# W512A.net
KiCad netlist of a schematic drawn in EAGLE
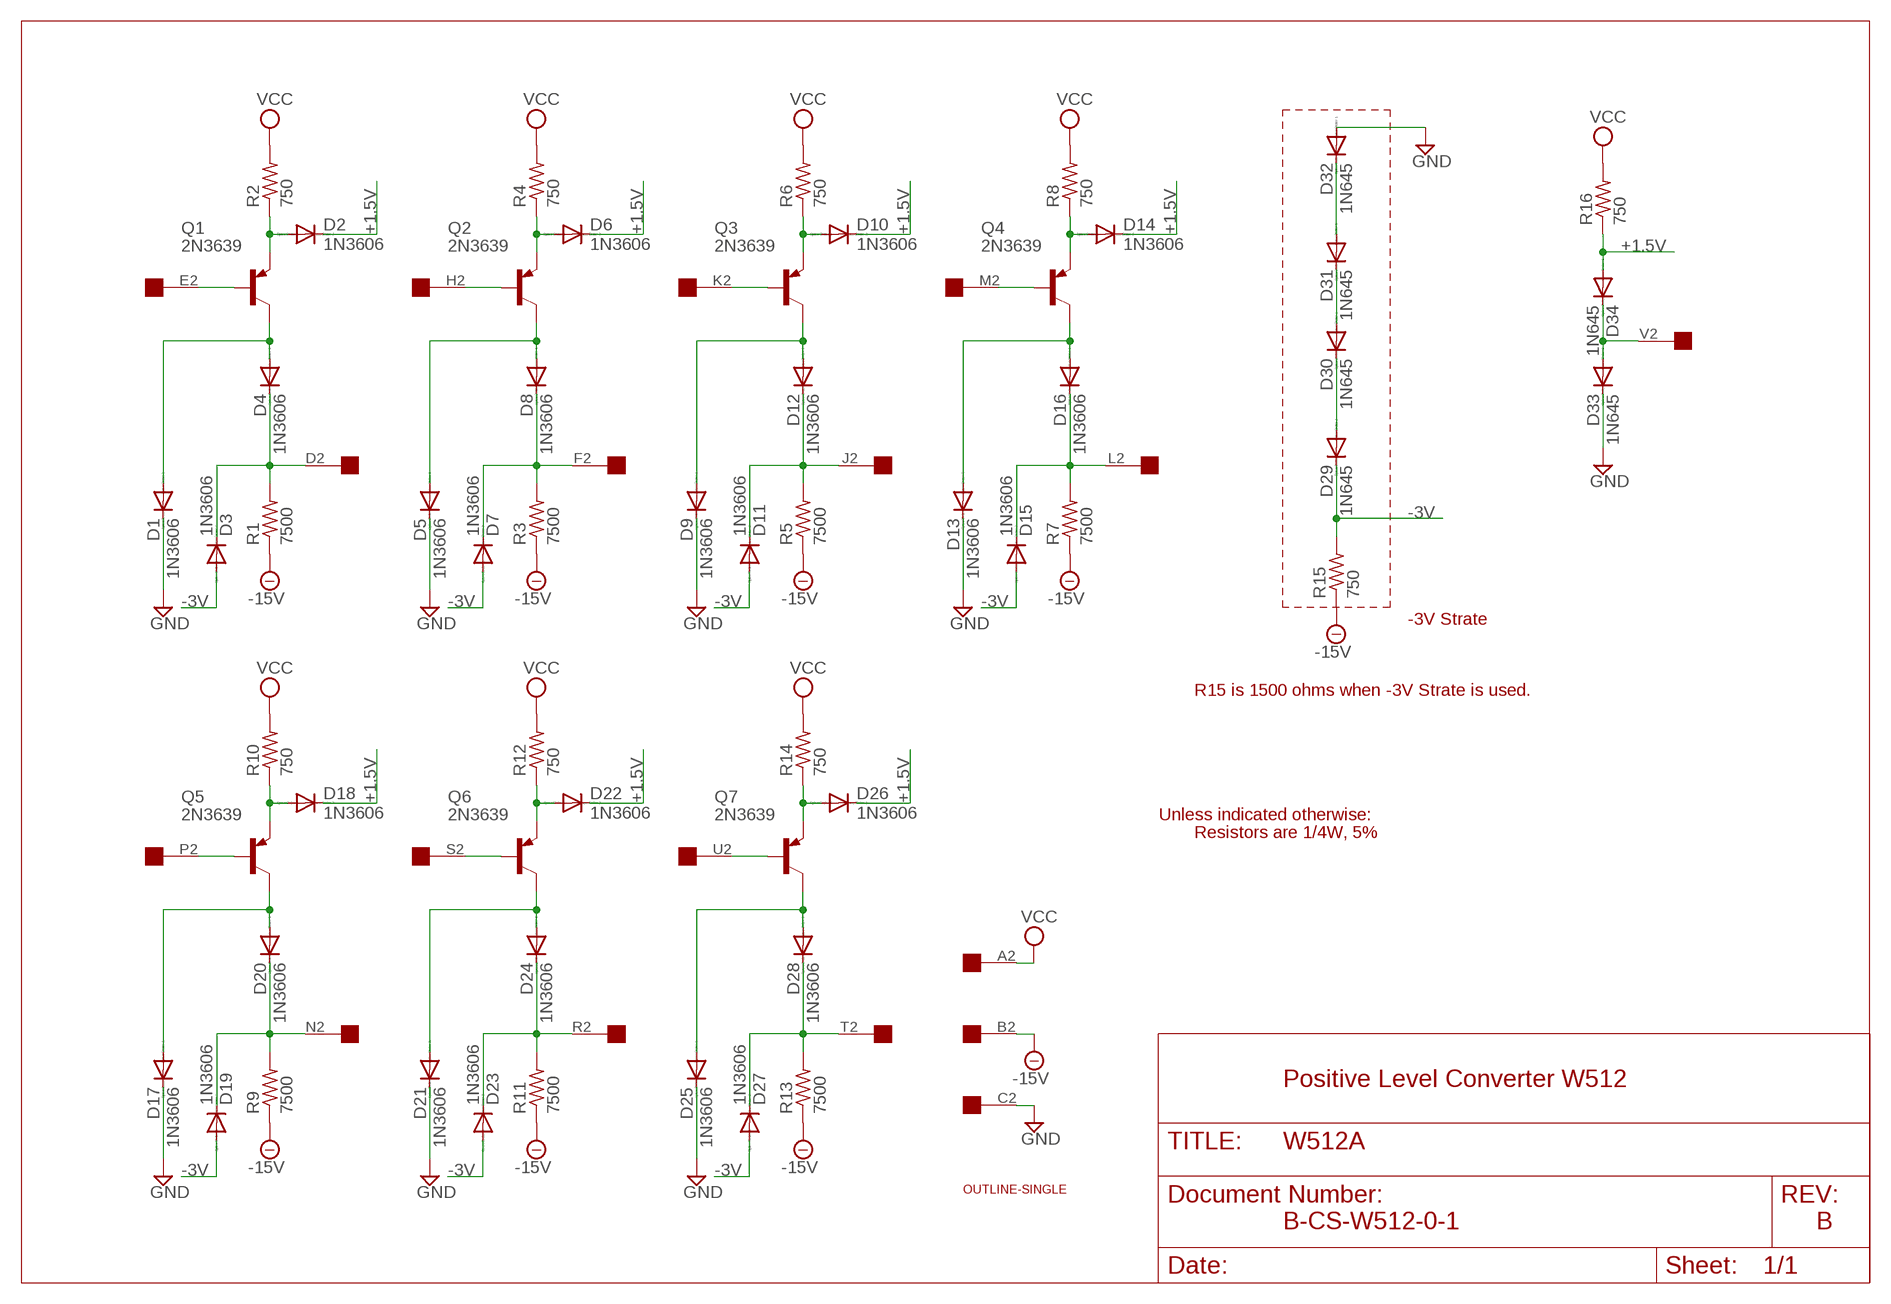
[diagram p0: schematic, sheet 1]

(export (version "E")
  (design (tool "Eeschema 10.0.6"))
  (components
    (comp (ref "D1")
      (value "1N3606")
      (footprint "eagle-import:DO35-10")
      (libsource (lib "eagle-import") (part "1N4148DO35-10"))
    )
    (comp (ref "D2")
      (value "1N3606")
      (footprint "eagle-import:DO35-10")
      (libsource (lib "eagle-import") (part "1N4148DO35-10"))
    )
    (comp (ref "D3")
      (value "1N3606")
      (footprint "eagle-import:DO35-10")
      (libsource (lib "eagle-import") (part "1N4148DO35-10"))
    )
    (comp (ref "D4")
      (value "1N3606")
      (footprint "eagle-import:DO35-10")
      (libsource (lib "eagle-import") (part "1N4148DO35-10"))
    )
    (comp (ref "D5")
      (value "1N3606")
      (footprint "eagle-import:DO35-10")
      (libsource (lib "eagle-import") (part "1N4148DO35-10"))
    )
    (comp (ref "D6")
      (value "1N3606")
      (footprint "eagle-import:DO35-10")
      (libsource (lib "eagle-import") (part "1N4148DO35-10"))
    )
    (comp (ref "D7")
      (value "1N3606")
      (footprint "eagle-import:DO35-10")
      (libsource (lib "eagle-import") (part "1N4148DO35-10"))
    )
    (comp (ref "D8")
      (value "1N3606")
      (footprint "eagle-import:DO35-10")
      (libsource (lib "eagle-import") (part "1N4148DO35-10"))
    )
    (comp (ref "D9")
      (value "1N3606")
      (footprint "eagle-import:DO35-10")
      (libsource (lib "eagle-import") (part "1N4148DO35-10"))
    )
    (comp (ref "D10")
      (value "1N3606")
      (footprint "eagle-import:DO35-10")
      (libsource (lib "eagle-import") (part "1N4148DO35-10"))
    )
    (comp (ref "D11")
      (value "1N3606")
      (footprint "eagle-import:DO35-10")
      (libsource (lib "eagle-import") (part "1N4148DO35-10"))
    )
    (comp (ref "D12")
      (value "1N3606")
      (footprint "eagle-import:DO35-10")
      (libsource (lib "eagle-import") (part "1N4148DO35-10"))
    )
    (comp (ref "D13")
      (value "1N3606")
      (footprint "eagle-import:DO35-10")
      (libsource (lib "eagle-import") (part "1N4148DO35-10"))
    )
    (comp (ref "D14")
      (value "1N3606")
      (footprint "eagle-import:DO35-10")
      (libsource (lib "eagle-import") (part "1N4148DO35-10"))
    )
    (comp (ref "D15")
      (value "1N3606")
      (footprint "eagle-import:DO35-10")
      (libsource (lib "eagle-import") (part "1N4148DO35-10"))
    )
    (comp (ref "D16")
      (value "1N3606")
      (footprint "eagle-import:DO35-10")
      (libsource (lib "eagle-import") (part "1N4148DO35-10"))
    )
    (comp (ref "D17")
      (value "1N3606")
      (footprint "eagle-import:DO35-10")
      (libsource (lib "eagle-import") (part "1N4148DO35-10"))
    )
    (comp (ref "D18")
      (value "1N3606")
      (footprint "eagle-import:DO35-10")
      (libsource (lib "eagle-import") (part "1N4148DO35-10"))
    )
    (comp (ref "D19")
      (value "1N3606")
      (footprint "eagle-import:DO35-10")
      (libsource (lib "eagle-import") (part "1N4148DO35-10"))
    )
    (comp (ref "D20")
      (value "1N3606")
      (footprint "eagle-import:DO35-10")
      (libsource (lib "eagle-import") (part "1N4148DO35-10"))
    )
    (comp (ref "D21")
      (value "1N3606")
      (footprint "eagle-import:DO35-10")
      (libsource (lib "eagle-import") (part "1N4148DO35-10"))
    )
    (comp (ref "D22")
      (value "1N3606")
      (footprint "eagle-import:DO35-10")
      (libsource (lib "eagle-import") (part "1N4148DO35-10"))
    )
    (comp (ref "D23")
      (value "1N3606")
      (footprint "eagle-import:DO35-10")
      (libsource (lib "eagle-import") (part "1N4148DO35-10"))
    )
    (comp (ref "D24")
      (value "1N3606")
      (footprint "eagle-import:DO35-10")
      (libsource (lib "eagle-import") (part "1N4148DO35-10"))
    )
    (comp (ref "D25")
      (value "1N3606")
      (footprint "eagle-import:DO35-10")
      (libsource (lib "eagle-import") (part "1N4148DO35-10"))
    )
    (comp (ref "D26")
      (value "1N3606")
      (footprint "eagle-import:DO35-10")
      (libsource (lib "eagle-import") (part "1N4148DO35-10"))
    )
    (comp (ref "D27")
      (value "1N3606")
      (footprint "eagle-import:DO35-10")
      (libsource (lib "eagle-import") (part "1N4148DO35-10"))
    )
    (comp (ref "D28")
      (value "1N3606")
      (footprint "eagle-import:DO35-10")
      (libsource (lib "eagle-import") (part "1N4148DO35-10"))
    )
    (comp (ref "D29")
      (value "1N645")
      (footprint "eagle-import:DO35-10")
      (libsource (lib "eagle-import") (part "1N4148DO35-10"))
    )
    (comp (ref "D30")
      (value "1N645")
      (footprint "eagle-import:DO35-10")
      (libsource (lib "eagle-import") (part "1N4148DO35-10"))
    )
    (comp (ref "D31")
      (value "1N645")
      (footprint "eagle-import:DO35-10")
      (libsource (lib "eagle-import") (part "1N4148DO35-10"))
    )
    (comp (ref "D32")
      (value "1N645")
      (footprint "eagle-import:DO35-10")
      (libsource (lib "eagle-import") (part "1N4148DO35-10"))
    )
    (comp (ref "D33")
      (value "1N645")
      (footprint "eagle-import:DO35-10")
      (libsource (lib "eagle-import") (part "1N4148DO35-10"))
    )
    (comp (ref "D34")
      (value "1N645")
      (footprint "eagle-import:DO35-10")
      (libsource (lib "eagle-import") (part "1N4148DO35-10"))
    )
    (comp (ref "EDGE")
      (value "EDGE-1")
      (footprint "eagle-import:EDGE-CON1")
      (libsource (lib "eagle-import") (part "EDGE-1"))
    )
    (comp (ref "Q1")
      (value "2N3639")
      (footprint "eagle-import:TO39")
      (libsource (lib "eagle-import") (part "2N2904"))
    )
    (comp (ref "Q2")
      (value "2N3639")
      (footprint "eagle-import:TO39")
      (libsource (lib "eagle-import") (part "2N2904"))
    )
    (comp (ref "Q3")
      (value "2N3639")
      (footprint "eagle-import:TO39")
      (libsource (lib "eagle-import") (part "2N2904"))
    )
    (comp (ref "Q4")
      (value "2N3639")
      (footprint "eagle-import:TO39")
      (libsource (lib "eagle-import") (part "2N2904"))
    )
    (comp (ref "Q5")
      (value "2N3639")
      (footprint "eagle-import:TO39")
      (libsource (lib "eagle-import") (part "2N2904"))
    )
    (comp (ref "Q6")
      (value "2N3639")
      (footprint "eagle-import:TO39")
      (libsource (lib "eagle-import") (part "2N2904"))
    )
    (comp (ref "Q7")
      (value "2N3639")
      (footprint "eagle-import:TO39")
      (libsource (lib "eagle-import") (part "2N2904"))
    )
    (comp (ref "R1")
      (value "7500")
      (footprint "eagle-import:0207_10")
      (libsource (lib "eagle-import") (part "R-US_0207/10"))
    )
    (comp (ref "R2")
      (value "750")
      (footprint "eagle-import:0207_10")
      (libsource (lib "eagle-import") (part "R-US_0207/10"))
    )
    (comp (ref "R3")
      (value "7500")
      (footprint "eagle-import:0207_10")
      (libsource (lib "eagle-import") (part "R-US_0207/10"))
    )
    (comp (ref "R4")
      (value "750")
      (footprint "eagle-import:0207_10")
      (libsource (lib "eagle-import") (part "R-US_0207/10"))
    )
    (comp (ref "R5")
      (value "7500")
      (footprint "eagle-import:0207_10")
      (libsource (lib "eagle-import") (part "R-US_0207/10"))
    )
    (comp (ref "R6")
      (value "750")
      (footprint "eagle-import:0207_10")
      (libsource (lib "eagle-import") (part "R-US_0207/10"))
    )
    (comp (ref "R7")
      (value "7500")
      (footprint "eagle-import:0207_10")
      (libsource (lib "eagle-import") (part "R-US_0207/10"))
    )
    (comp (ref "R8")
      (value "750")
      (footprint "eagle-import:0207_10")
      (libsource (lib "eagle-import") (part "R-US_0207/10"))
    )
    (comp (ref "R9")
      (value "7500")
      (footprint "eagle-import:0207_10")
      (libsource (lib "eagle-import") (part "R-US_0207/10"))
    )
    (comp (ref "R10")
      (value "750")
      (footprint "eagle-import:0207_10")
      (libsource (lib "eagle-import") (part "R-US_0207/10"))
    )
    (comp (ref "R11")
      (value "7500")
      (footprint "eagle-import:0207_10")
      (libsource (lib "eagle-import") (part "R-US_0207/10"))
    )
    (comp (ref "R12")
      (value "750")
      (footprint "eagle-import:0207_10")
      (libsource (lib "eagle-import") (part "R-US_0207/10"))
    )
    (comp (ref "R13")
      (value "7500")
      (footprint "eagle-import:0207_10")
      (libsource (lib "eagle-import") (part "R-US_0207/10"))
    )
    (comp (ref "R14")
      (value "750")
      (footprint "eagle-import:0207_10")
      (libsource (lib "eagle-import") (part "R-US_0207/10"))
    )
    (comp (ref "R15")
      (value "750")
      (footprint "eagle-import:0207_10")
      (libsource (lib "eagle-import") (part "R-US_0207/10"))
    )
    (comp (ref "R16")
      (value "750")
      (footprint "eagle-import:0207_10")
      (libsource (lib "eagle-import") (part "R-US_0207/10"))
    )
    (comp (ref "U$1")
      (value "OUTLINE-SINGLE")
      (footprint "eagle-import:SINGLE")
      (libsource (lib "eagle-import") (part "OUTLINE-SINGLE"))
    )
  )
  (nets
    (net (code "1") (name "-15V") (class "Default")
      (node (ref "EDGE") (pin "B2") (pinfunction "1_B2") (pintype "bidirectional"))
      (node (ref "R1") (pin "1") (pinfunction "1_1") (pintype "passive"))
      (node (ref "R11") (pin "1") (pinfunction "1_1") (pintype "passive"))
      (node (ref "R13") (pin "1") (pinfunction "1_1") (pintype "passive"))
      (node (ref "R15") (pin "1") (pinfunction "1_1") (pintype "passive"))
      (node (ref "R3") (pin "1") (pinfunction "1_1") (pintype "passive"))
      (node (ref "R5") (pin "1") (pinfunction "1_1") (pintype "passive"))
      (node (ref "R7") (pin "1") (pinfunction "1_1") (pintype "passive"))
      (node (ref "R9") (pin "1") (pinfunction "1_1") (pintype "passive"))
    )
    (net (code "2") (name "/+1.5V") (class "Default")
      (node (ref "D10") (pin "C") (pinfunction "C_C") (pintype "passive"))
      (node (ref "D14") (pin "C") (pinfunction "C_C") (pintype "passive"))
      (node (ref "D18") (pin "C") (pinfunction "C_C") (pintype "passive"))
      (node (ref "D2") (pin "C") (pinfunction "C_C") (pintype "passive"))
      (node (ref "D22") (pin "C") (pinfunction "C_C") (pintype "passive"))
      (node (ref "D26") (pin "C") (pinfunction "C_C") (pintype "passive"))
      (node (ref "D34") (pin "A") (pinfunction "A_A") (pintype "passive"))
      (node (ref "D6") (pin "C") (pinfunction "C_C") (pintype "passive"))
      (node (ref "R16") (pin "1") (pinfunction "1_1") (pintype "passive"))
    )
    (net (code "3") (name "/-3V") (class "Default")
      (node (ref "D11") (pin "A") (pinfunction "A_A") (pintype "passive"))
      (node (ref "D15") (pin "A") (pinfunction "A_A") (pintype "passive"))
      (node (ref "D19") (pin "A") (pinfunction "A_A") (pintype "passive"))
      (node (ref "D23") (pin "A") (pinfunction "A_A") (pintype "passive"))
      (node (ref "D27") (pin "A") (pinfunction "A_A") (pintype "passive"))
      (node (ref "D29") (pin "C") (pinfunction "C_C") (pintype "passive"))
      (node (ref "D3") (pin "A") (pinfunction "A_A") (pintype "passive"))
      (node (ref "D7") (pin "A") (pinfunction "A_A") (pintype "passive"))
      (node (ref "R15") (pin "2") (pinfunction "2_2") (pintype "passive"))
    )
    (net (code "4") (name "GND") (class "Default")
      (node (ref "D1") (pin "C") (pinfunction "C_C") (pintype "passive"))
      (node (ref "D13") (pin "C") (pinfunction "C_C") (pintype "passive"))
      (node (ref "D17") (pin "C") (pinfunction "C_C") (pintype "passive"))
      (node (ref "D21") (pin "C") (pinfunction "C_C") (pintype "passive"))
      (node (ref "D25") (pin "C") (pinfunction "C_C") (pintype "passive"))
      (node (ref "D32") (pin "A") (pinfunction "A_A") (pintype "passive"))
      (node (ref "D33") (pin "C") (pinfunction "C_C") (pintype "passive"))
      (node (ref "D5") (pin "C") (pinfunction "C_C") (pintype "passive"))
      (node (ref "D9") (pin "C") (pinfunction "C_C") (pintype "passive"))
      (node (ref "EDGE") (pin "C2") (pinfunction "1_C2") (pintype "bidirectional"))
    )
    (net (code "5") (name "Net-(D29-PadA)") (class "Default")
      (node (ref "D29") (pin "A") (pinfunction "A_A") (pintype "passive"))
      (node (ref "D30") (pin "C") (pinfunction "C_C") (pintype "passive"))
    )
    (net (code "6") (name "Net-(D30-PadA)") (class "Default")
      (node (ref "D30") (pin "A") (pinfunction "A_A") (pintype "passive"))
      (node (ref "D31") (pin "C") (pinfunction "C_C") (pintype "passive"))
    )
    (net (code "7") (name "Net-(D31-PadA)") (class "Default")
      (node (ref "D31") (pin "A") (pinfunction "A_A") (pintype "passive"))
      (node (ref "D32") (pin "C") (pinfunction "C_C") (pintype "passive"))
    )
    (net (code "8") (name "Net-(EDGED-1)") (class "Default")
      (node (ref "D3") (pin "C") (pinfunction "C_C") (pintype "passive"))
      (node (ref "D4") (pin "C") (pinfunction "C_C") (pintype "passive"))
      (node (ref "EDGE") (pin "D2") (pinfunction "1_D2") (pintype "bidirectional"))
      (node (ref "R1") (pin "2") (pinfunction "2_2") (pintype "passive"))
    )
    (net (code "9") (name "Net-(EDGEE-1)") (class "Default")
      (node (ref "EDGE") (pin "E2") (pinfunction "1_E2") (pintype "bidirectional"))
      (node (ref "Q1") (pin "2") (pinfunction "B_2") (pintype "passive"))
    )
    (net (code "10") (name "Net-(EDGEF-1)") (class "Default")
      (node (ref "D7") (pin "C") (pinfunction "C_C") (pintype "passive"))
      (node (ref "D8") (pin "C") (pinfunction "C_C") (pintype "passive"))
      (node (ref "EDGE") (pin "F2") (pinfunction "1_F2") (pintype "bidirectional"))
      (node (ref "R3") (pin "2") (pinfunction "2_2") (pintype "passive"))
    )
    (net (code "11") (name "Net-(EDGEG-1)") (class "Default")
      (node (ref "EDGE") (pin "H2") (pinfunction "1_H2") (pintype "bidirectional"))
      (node (ref "Q2") (pin "2") (pinfunction "B_2") (pintype "passive"))
    )
    (net (code "12") (name "Net-(EDGEH-1)") (class "Default")
      (node (ref "D11") (pin "C") (pinfunction "C_C") (pintype "passive"))
      (node (ref "D12") (pin "C") (pinfunction "C_C") (pintype "passive"))
      (node (ref "EDGE") (pin "J2") (pinfunction "1_J2") (pintype "bidirectional"))
      (node (ref "R5") (pin "2") (pinfunction "2_2") (pintype "passive"))
    )
    (net (code "13") (name "Net-(EDGEI-1)") (class "Default")
      (node (ref "EDGE") (pin "K2") (pinfunction "1_K2") (pintype "bidirectional"))
      (node (ref "Q3") (pin "2") (pinfunction "B_2") (pintype "passive"))
    )
    (net (code "14") (name "Net-(EDGEJ-1)") (class "Default")
      (node (ref "D15") (pin "C") (pinfunction "C_C") (pintype "passive"))
      (node (ref "D16") (pin "C") (pinfunction "C_C") (pintype "passive"))
      (node (ref "EDGE") (pin "L2") (pinfunction "1_L2") (pintype "bidirectional"))
      (node (ref "R7") (pin "2") (pinfunction "2_2") (pintype "passive"))
    )
    (net (code "15") (name "Net-(EDGEK-1)") (class "Default")
      (node (ref "EDGE") (pin "M2") (pinfunction "1_M2") (pintype "bidirectional"))
      (node (ref "Q4") (pin "2") (pinfunction "B_2") (pintype "passive"))
    )
    (net (code "16") (name "Net-(EDGEL-1)") (class "Default")
      (node (ref "D19") (pin "C") (pinfunction "C_C") (pintype "passive"))
      (node (ref "D20") (pin "C") (pinfunction "C_C") (pintype "passive"))
      (node (ref "EDGE") (pin "N2") (pinfunction "1_N2") (pintype "bidirectional"))
      (node (ref "R9") (pin "2") (pinfunction "2_2") (pintype "passive"))
    )
    (net (code "17") (name "Net-(EDGEM-1)") (class "Default")
      (node (ref "EDGE") (pin "P2") (pinfunction "1_P2") (pintype "bidirectional"))
      (node (ref "Q5") (pin "2") (pinfunction "B_2") (pintype "passive"))
    )
    (net (code "18") (name "Net-(EDGEN-1)") (class "Default")
      (node (ref "D23") (pin "C") (pinfunction "C_C") (pintype "passive"))
      (node (ref "D24") (pin "C") (pinfunction "C_C") (pintype "passive"))
      (node (ref "EDGE") (pin "R2") (pinfunction "1_R2") (pintype "bidirectional"))
      (node (ref "R11") (pin "2") (pinfunction "2_2") (pintype "passive"))
    )
    (net (code "19") (name "Net-(EDGEO-1)") (class "Default")
      (node (ref "EDGE") (pin "S2") (pinfunction "1_S2") (pintype "bidirectional"))
      (node (ref "Q6") (pin "2") (pinfunction "B_2") (pintype "passive"))
    )
    (net (code "20") (name "Net-(EDGEP-1)") (class "Default")
      (node (ref "D27") (pin "C") (pinfunction "C_C") (pintype "passive"))
      (node (ref "D28") (pin "C") (pinfunction "C_C") (pintype "passive"))
      (node (ref "EDGE") (pin "T2") (pinfunction "1_T2") (pintype "bidirectional"))
      (node (ref "R13") (pin "2") (pinfunction "2_2") (pintype "passive"))
    )
    (net (code "21") (name "Net-(EDGEQ-1)") (class "Default")
      (node (ref "EDGE") (pin "U2") (pinfunction "1_U2") (pintype "bidirectional"))
      (node (ref "Q7") (pin "2") (pinfunction "B_2") (pintype "passive"))
    )
    (net (code "22") (name "Net-(EDGER-1)") (class "Default")
      (node (ref "D33") (pin "A") (pinfunction "A_A") (pintype "passive"))
      (node (ref "D34") (pin "C") (pinfunction "C_C") (pintype "passive"))
      (node (ref "EDGE") (pin "V2") (pinfunction "1_V2") (pintype "bidirectional"))
    )
    (net (code "23") (name "Net-(Q1-C)") (class "Default")
      (node (ref "D1") (pin "A") (pinfunction "A_A") (pintype "passive"))
      (node (ref "D4") (pin "A") (pinfunction "A_A") (pintype "passive"))
      (node (ref "Q1") (pin "3") (pinfunction "C_3") (pintype "passive"))
    )
    (net (code "24") (name "Net-(Q1-E)") (class "Default")
      (node (ref "D2") (pin "A") (pinfunction "A_A") (pintype "passive"))
      (node (ref "Q1") (pin "1") (pinfunction "E_1") (pintype "passive"))
      (node (ref "R2") (pin "1") (pinfunction "1_1") (pintype "passive"))
    )
    (net (code "25") (name "Net-(Q2-C)") (class "Default")
      (node (ref "D5") (pin "A") (pinfunction "A_A") (pintype "passive"))
      (node (ref "D8") (pin "A") (pinfunction "A_A") (pintype "passive"))
      (node (ref "Q2") (pin "3") (pinfunction "C_3") (pintype "passive"))
    )
    (net (code "26") (name "Net-(Q2-E)") (class "Default")
      (node (ref "D6") (pin "A") (pinfunction "A_A") (pintype "passive"))
      (node (ref "Q2") (pin "1") (pinfunction "E_1") (pintype "passive"))
      (node (ref "R4") (pin "1") (pinfunction "1_1") (pintype "passive"))
    )
    (net (code "27") (name "Net-(Q3-C)") (class "Default")
      (node (ref "D12") (pin "A") (pinfunction "A_A") (pintype "passive"))
      (node (ref "D9") (pin "A") (pinfunction "A_A") (pintype "passive"))
      (node (ref "Q3") (pin "3") (pinfunction "C_3") (pintype "passive"))
    )
    (net (code "28") (name "Net-(Q3-E)") (class "Default")
      (node (ref "D10") (pin "A") (pinfunction "A_A") (pintype "passive"))
      (node (ref "Q3") (pin "1") (pinfunction "E_1") (pintype "passive"))
      (node (ref "R6") (pin "1") (pinfunction "1_1") (pintype "passive"))
    )
    (net (code "29") (name "Net-(Q4-C)") (class "Default")
      (node (ref "D13") (pin "A") (pinfunction "A_A") (pintype "passive"))
      (node (ref "D16") (pin "A") (pinfunction "A_A") (pintype "passive"))
      (node (ref "Q4") (pin "3") (pinfunction "C_3") (pintype "passive"))
    )
    (net (code "30") (name "Net-(Q4-E)") (class "Default")
      (node (ref "D14") (pin "A") (pinfunction "A_A") (pintype "passive"))
      (node (ref "Q4") (pin "1") (pinfunction "E_1") (pintype "passive"))
      (node (ref "R8") (pin "1") (pinfunction "1_1") (pintype "passive"))
    )
    (net (code "31") (name "Net-(Q5-C)") (class "Default")
      (node (ref "D17") (pin "A") (pinfunction "A_A") (pintype "passive"))
      (node (ref "D20") (pin "A") (pinfunction "A_A") (pintype "passive"))
      (node (ref "Q5") (pin "3") (pinfunction "C_3") (pintype "passive"))
    )
    (net (code "32") (name "Net-(Q5-E)") (class "Default")
      (node (ref "D18") (pin "A") (pinfunction "A_A") (pintype "passive"))
      (node (ref "Q5") (pin "1") (pinfunction "E_1") (pintype "passive"))
      (node (ref "R10") (pin "1") (pinfunction "1_1") (pintype "passive"))
    )
    (net (code "33") (name "Net-(Q6-C)") (class "Default")
      (node (ref "D21") (pin "A") (pinfunction "A_A") (pintype "passive"))
      (node (ref "D24") (pin "A") (pinfunction "A_A") (pintype "passive"))
      (node (ref "Q6") (pin "3") (pinfunction "C_3") (pintype "passive"))
    )
    (net (code "34") (name "Net-(Q6-E)") (class "Default")
      (node (ref "D22") (pin "A") (pinfunction "A_A") (pintype "passive"))
      (node (ref "Q6") (pin "1") (pinfunction "E_1") (pintype "passive"))
      (node (ref "R12") (pin "1") (pinfunction "1_1") (pintype "passive"))
    )
    (net (code "35") (name "Net-(Q7-C)") (class "Default")
      (node (ref "D25") (pin "A") (pinfunction "A_A") (pintype "passive"))
      (node (ref "D28") (pin "A") (pinfunction "A_A") (pintype "passive"))
      (node (ref "Q7") (pin "3") (pinfunction "C_3") (pintype "passive"))
    )
    (net (code "36") (name "Net-(Q7-E)") (class "Default")
      (node (ref "D26") (pin "A") (pinfunction "A_A") (pintype "passive"))
      (node (ref "Q7") (pin "1") (pinfunction "E_1") (pintype "passive"))
      (node (ref "R14") (pin "1") (pinfunction "1_1") (pintype "passive"))
    )
    (net (code "37") (name "VCC") (class "Default")
      (node (ref "EDGE") (pin "A2") (pinfunction "1_A2") (pintype "bidirectional"))
      (node (ref "R10") (pin "2") (pinfunction "2_2") (pintype "passive"))
      (node (ref "R12") (pin "2") (pinfunction "2_2") (pintype "passive"))
      (node (ref "R14") (pin "2") (pinfunction "2_2") (pintype "passive"))
      (node (ref "R16") (pin "2") (pinfunction "2_2") (pintype "passive"))
      (node (ref "R2") (pin "2") (pinfunction "2_2") (pintype "passive"))
      (node (ref "R4") (pin "2") (pinfunction "2_2") (pintype "passive"))
      (node (ref "R6") (pin "2") (pinfunction "2_2") (pintype "passive"))
      (node (ref "R8") (pin "2") (pinfunction "2_2") (pintype "passive"))
    )
  )
)
